# 1s.net
KiCad netlist of a schematic drawn in EAGLE
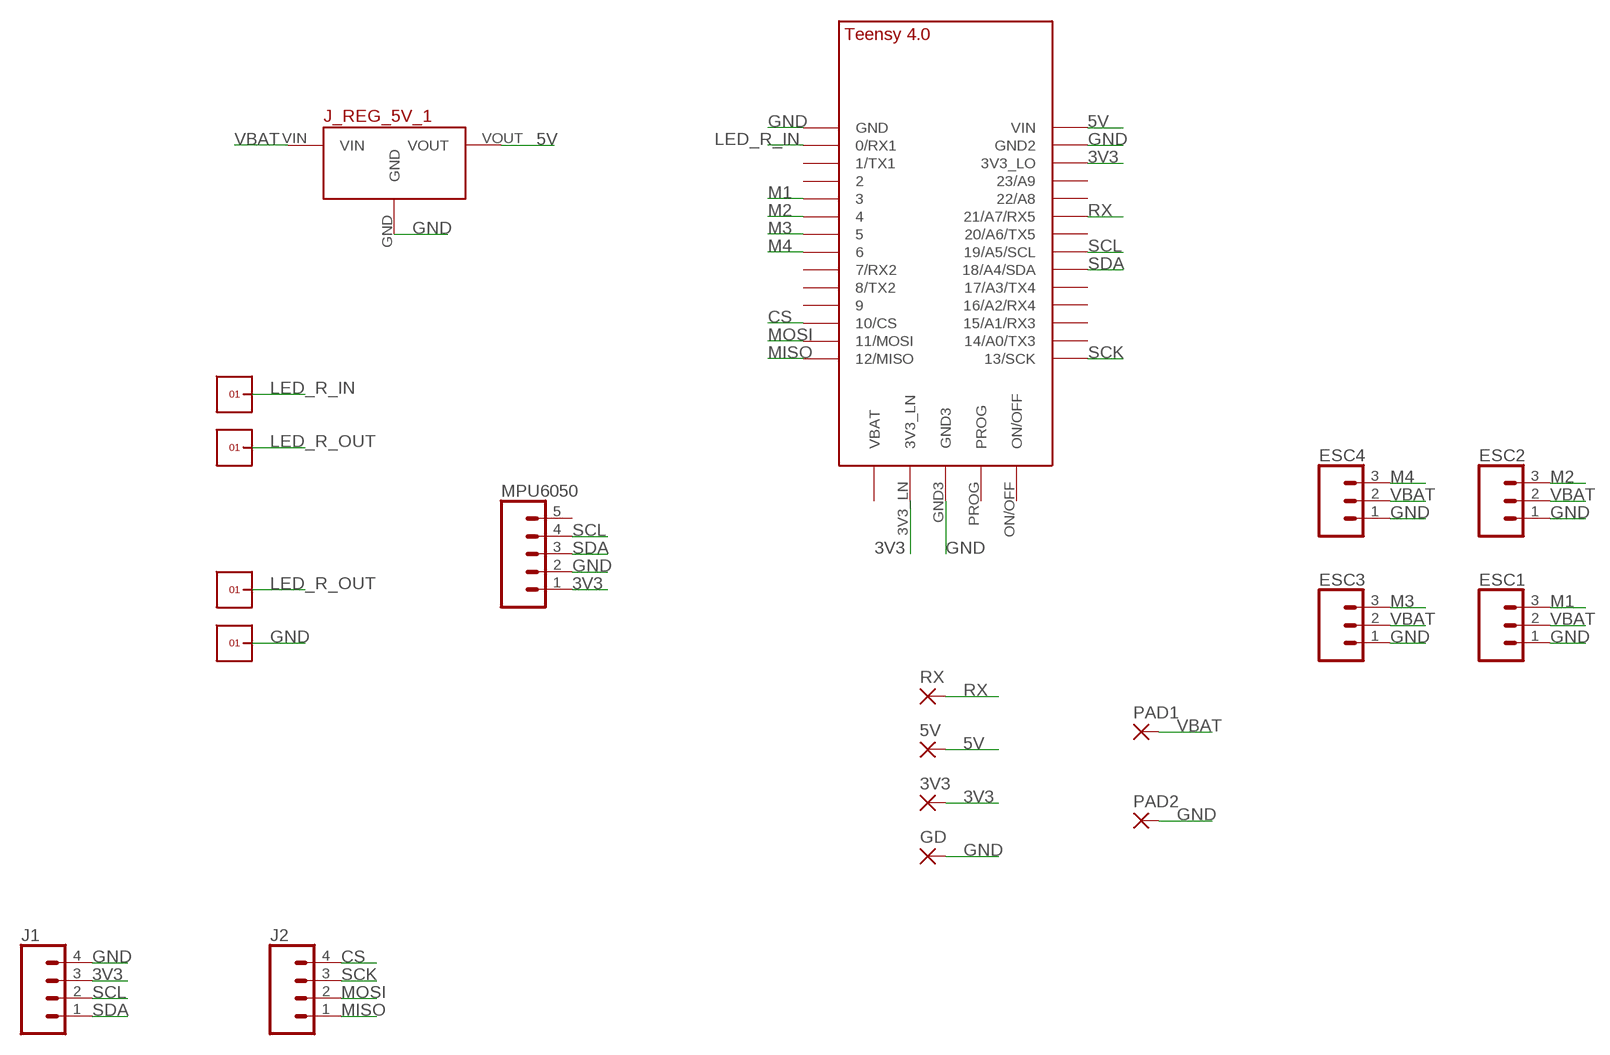
[diagram p0: schematic, sheet 1]

(export (version "E")
  (design (tool "Eeschema 10.0.6"))
  (components
    (comp (ref "3V3")
      (value "SMD2")
      (footprint "eagle-import:SMD1,27-2,54")
      (libsource (lib "eagle-import") (part "SMD2"))
    )
    (comp (ref "5V")
      (value "SMD2")
      (footprint "eagle-import:SMD1,27-2,54")
      (libsource (lib "eagle-import") (part "SMD2"))
    )
    (comp (ref "ESC1")
      (value "455-1750-1-ND")
      (footprint "eagle-import:1X03")
      (libsource (lib "eagle-import") (part "CONN_03"))
    )
    (comp (ref "ESC2")
      (value "455-1750-1-ND")
      (footprint "eagle-import:1X03")
      (libsource (lib "eagle-import") (part "CONN_03"))
    )
    (comp (ref "ESC3")
      (value "455-1750-1-ND")
      (footprint "eagle-import:1X03")
      (libsource (lib "eagle-import") (part "CONN_03"))
    )
    (comp (ref "ESC4")
      (value "455-1750-1-ND")
      (footprint "eagle-import:1X03")
      (libsource (lib "eagle-import") (part "CONN_03"))
    )
    (comp (ref "GD")
      (value "SMD2")
      (footprint "eagle-import:SMD1,27-2,54")
      (libsource (lib "eagle-import") (part "SMD2"))
    )
    (comp (ref "J1")
      (value "CONN_041X04_NO_SILK")
      (footprint "eagle-import:1X04_NO_SILK")
      (libsource (lib "eagle-import") (part "CONN_041X04_NO_SILK"))
    )
    (comp (ref "J2")
      (value "CONN_041X04_NO_SILK")
      (footprint "eagle-import:1X04_NO_SILK")
      (libsource (lib "eagle-import") (part "CONN_041X04_NO_SILK"))
    )
    (comp (ref "J_REG_5V_1")
      (value "5V_VOLTAGE_REGULATOR")
      (footprint "eagle-import:5V_VOLTAGE_REGULATOR")
      (libsource (lib "eagle-import") (part "5V_VOLTAGE_REGULATOR"))
    )
    (comp (ref "MPU6050")
      (value "CONN_05NO_SILK")
      (footprint "eagle-import:1X05_NO_SILK")
      (libsource (lib "eagle-import") (part "CONN_05NO_SILK"))
    )
    (comp (ref "PAD1")
      (value "SMD5")
      (footprint "eagle-import:SMD2,54-5,08")
      (libsource (lib "eagle-import") (part "SMD5"))
    )
    (comp (ref "PAD2")
      (value "SMD5")
      (footprint "eagle-import:SMD2,54-5,08")
      (libsource (lib "eagle-import") (part "SMD5"))
    )
    (comp (ref "RX")
      (value "SMD2")
      (footprint "eagle-import:SMD1,27-2,54")
      (libsource (lib "eagle-import") (part "SMD2"))
    )
    (comp (ref "U$1")
      (value "TEENSY_4.0")
      (footprint "eagle-import:TEENSY_4.0")
      (libsource (lib "eagle-import") (part "TEENSY_4.0"))
    )
    (comp (ref "U$3")
      (value "1X1")
      (footprint "eagle-import:1X1")
      (libsource (lib "eagle-import") (part "1X1"))
    )
    (comp (ref "U$4")
      (value "1X1")
      (footprint "eagle-import:1X1")
      (libsource (lib "eagle-import") (part "1X1"))
    )
    (comp (ref "U$6")
      (value "1X1")
      (footprint "eagle-import:1X1")
      (libsource (lib "eagle-import") (part "1X1"))
    )
    (comp (ref "U$7")
      (value "1X1")
      (footprint "eagle-import:1X1")
      (libsource (lib "eagle-import") (part "1X1"))
    )
  )
  (nets
    (net (code "1") (name "/3V3") (class "Default")
      (node (ref "3V3") (pin "1") (pinfunction "P_1") (pintype "passive"))
      (node (ref "J1") (pin "3") (pinfunction "3_3") (pintype "passive"))
      (node (ref "MPU6050") (pin "1") (pinfunction "1_1") (pintype "passive"))
      (node (ref "U$1") (pin "3V3_LN") (pinfunction "3V3_LN_3V3_LN") (pintype "bidirectional"))
      (node (ref "U$1") (pin "3V3_LO") (pinfunction "3V3_LO_3V3_LO") (pintype "bidirectional"))
    )
    (net (code "2") (name "/5V") (class "Default")
      (node (ref "5V") (pin "1") (pinfunction "P_1") (pintype "passive"))
      (node (ref "J_REG_5V_1") (pin "VOUT") (pinfunction "VOUT_VOUT") (pintype "bidirectional"))
      (node (ref "U$1") (pin "VIN") (pinfunction "VIN_VIN") (pintype "bidirectional"))
    )
    (net (code "3") (name "/CS") (class "Default")
      (node (ref "J2") (pin "4") (pinfunction "4_4") (pintype "passive"))
      (node (ref "U$1") (pin "10/CS") (pinfunction "10/CS_10/CS") (pintype "bidirectional"))
    )
    (net (code "4") (name "/GND") (class "Default")
      (node (ref "ESC1") (pin "1") (pinfunction "1_1") (pintype "passive"))
      (node (ref "ESC2") (pin "1") (pinfunction "1_1") (pintype "passive"))
      (node (ref "ESC3") (pin "1") (pinfunction "1_1") (pintype "passive"))
      (node (ref "ESC4") (pin "1") (pinfunction "1_1") (pintype "passive"))
      (node (ref "GD") (pin "1") (pinfunction "P_1") (pintype "passive"))
      (node (ref "J1") (pin "4") (pinfunction "4_4") (pintype "passive"))
      (node (ref "J_REG_5V_1") (pin "GND") (pinfunction "GND_GND") (pintype "bidirectional"))
      (node (ref "MPU6050") (pin "2") (pinfunction "2_2") (pintype "passive"))
      (node (ref "PAD2") (pin "1") (pinfunction "P_1") (pintype "passive"))
      (node (ref "U$1") (pin "GND") (pinfunction "GND_GND") (pintype "bidirectional"))
      (node (ref "U$1") (pin "GND2") (pinfunction "GND2_GND2") (pintype "bidirectional"))
      (node (ref "U$1") (pin "GND3") (pinfunction "GND3_GND3") (pintype "bidirectional"))
      (node (ref "U$7") (pin "1") (pinfunction "1_1") (pintype "bidirectional"))
    )
    (net (code "5") (name "/LED_R_IN") (class "Default")
      (node (ref "U$1") (pin "0/RX") (pinfunction "0/RX1_0/RX") (pintype "bidirectional"))
      (node (ref "U$3") (pin "1") (pinfunction "1_1") (pintype "bidirectional"))
    )
    (net (code "6") (name "/LED_R_OUT") (class "Default")
      (node (ref "U$4") (pin "1") (pinfunction "1_1") (pintype "bidirectional"))
      (node (ref "U$6") (pin "1") (pinfunction "1_1") (pintype "bidirectional"))
    )
    (net (code "7") (name "/M1") (class "Default")
      (node (ref "ESC1") (pin "3") (pinfunction "3_3") (pintype "passive"))
      (node (ref "U$1") (pin "3/CANTX") (pinfunction "3_3/CANTX") (pintype "bidirectional"))
    )
    (net (code "8") (name "/M2") (class "Default")
      (node (ref "ESC2") (pin "3") (pinfunction "3_3") (pintype "passive"))
      (node (ref "U$1") (pin "4/CANRX") (pinfunction "4_4/CANRX") (pintype "bidirectional"))
    )
    (net (code "9") (name "/M3") (class "Default")
      (node (ref "ESC3") (pin "3") (pinfunction "3_3") (pintype "passive"))
      (node (ref "U$1") (pin "5") (pinfunction "5_5") (pintype "bidirectional"))
    )
    (net (code "10") (name "/M4") (class "Default")
      (node (ref "ESC4") (pin "3") (pinfunction "3_3") (pintype "passive"))
      (node (ref "U$1") (pin "6") (pinfunction "6_6") (pintype "bidirectional"))
    )
    (net (code "11") (name "/MISO") (class "Default")
      (node (ref "J2") (pin "1") (pinfunction "1_1") (pintype "passive"))
      (node (ref "U$1") (pin "12/MISO") (pinfunction "12/MISO_12/MISO") (pintype "bidirectional"))
    )
    (net (code "12") (name "/MOSI") (class "Default")
      (node (ref "J2") (pin "2") (pinfunction "2_2") (pintype "passive"))
      (node (ref "U$1") (pin "11/MOSI") (pinfunction "11/MOSI_11/MOSI") (pintype "bidirectional"))
    )
    (net (code "13") (name "/RX") (class "Default")
      (node (ref "RX") (pin "1") (pinfunction "P_1") (pintype "passive"))
      (node (ref "U$1") (pin "21/A7") (pinfunction "21/A7/RX5_21/A7") (pintype "bidirectional"))
    )
    (net (code "14") (name "/SCK") (class "Default")
      (node (ref "J2") (pin "3") (pinfunction "3_3") (pintype "passive"))
      (node (ref "U$1") (pin "13/SCK") (pinfunction "13/SCK_13/SCK") (pintype "bidirectional"))
    )
    (net (code "15") (name "/SCL") (class "Default")
      (node (ref "J1") (pin "2") (pinfunction "2_2") (pintype "passive"))
      (node (ref "MPU6050") (pin "4") (pinfunction "4_4") (pintype "passive"))
      (node (ref "U$1") (pin "19/A5/SCL") (pinfunction "19/A5/SCL_19/A5/SCL") (pintype "bidirectional"))
    )
    (net (code "16") (name "/SDA") (class "Default")
      (node (ref "J1") (pin "1") (pinfunction "1_1") (pintype "passive"))
      (node (ref "MPU6050") (pin "3") (pinfunction "3_3") (pintype "passive"))
      (node (ref "U$1") (pin "18/A4/SDA") (pinfunction "18/A4/SDA_18/A4/SDA") (pintype "bidirectional"))
    )
    (net (code "17") (name "/VBAT") (class "Default")
      (node (ref "ESC1") (pin "2") (pinfunction "2_2") (pintype "passive"))
      (node (ref "ESC2") (pin "2") (pinfunction "2_2") (pintype "passive"))
      (node (ref "ESC3") (pin "2") (pinfunction "2_2") (pintype "passive"))
      (node (ref "ESC4") (pin "2") (pinfunction "2_2") (pintype "passive"))
      (node (ref "J_REG_5V_1") (pin "VIN") (pinfunction "VIN_VIN") (pintype "bidirectional"))
      (node (ref "PAD1") (pin "1") (pinfunction "P_1") (pintype "passive"))
    )
    (net (code "18") (name "unconnected-(MPU6050-Pad5)") (class "Default")
      (node (ref "MPU6050") (pin "5") (pinfunction "5_5") (pintype "passive"))
    )
    (net (code "19") (name "unconnected-(U$1-1{slash}TX1-Pad1{slash}TX)") (class "Default")
      (node (ref "U$1") (pin "1/TX") (pinfunction "1/TX1_1/TX") (pintype "bidirectional"))
    )
    (net (code "20") (name "unconnected-(U$1-7{slash}RX2-Pad7)") (class "Default")
      (node (ref "U$1") (pin "7") (pinfunction "7/RX2_7") (pintype "bidirectional"))
    )
    (net (code "21") (name "unconnected-(U$1-8{slash}TX2-Pad8)") (class "Default")
      (node (ref "U$1") (pin "8") (pinfunction "8/TX2_8") (pintype "bidirectional"))
    )
    (net (code "22") (name "unconnected-(U$1-9-Pad9{slash}CS)") (class "Default")
      (node (ref "U$1") (pin "9/CS") (pinfunction "9_9/CS") (pintype "bidirectional"))
    )
    (net (code "23") (name "unconnected-(U$1-14{slash}A0{slash}TX3-Pad14{slash}A0)") (class "Default")
      (node (ref "U$1") (pin "14/A0") (pinfunction "14/A0/TX3_14/A0") (pintype "bidirectional"))
    )
    (net (code "24") (name "unconnected-(U$1-15{slash}A1{slash}RX3-Pad15{slash}A1)") (class "Default")
      (node (ref "U$1") (pin "15/A1") (pinfunction "15/A1/RX3_15/A1") (pintype "bidirectional"))
    )
    (net (code "25") (name "unconnected-(U$1-16{slash}A2{slash}RX4-Pad16{slash}A2)") (class "Default")
      (node (ref "U$1") (pin "16/A2") (pinfunction "16/A2/RX4_16/A2") (pintype "bidirectional"))
    )
    (net (code "26") (name "unconnected-(U$1-17{slash}A3{slash}TX4-Pad17{slash}A3)") (class "Default")
      (node (ref "U$1") (pin "17/A3") (pinfunction "17/A3/TX4_17/A3") (pintype "bidirectional"))
    )
    (net (code "27") (name "unconnected-(U$1-20{slash}A6{slash}TX5-Pad20{slash}A6)") (class "Default")
      (node (ref "U$1") (pin "20/A6") (pinfunction "20/A6/TX5_20/A6") (pintype "bidirectional"))
    )
    (net (code "28") (name "unconnected-(U$1-Pad2)") (class "Default")
      (node (ref "U$1") (pin "2") (pinfunction "2_2") (pintype "bidirectional"))
    )
    (net (code "29") (name "unconnected-(U$1-Pad22{slash}A8)") (class "Default")
      (node (ref "U$1") (pin "22/A8") (pinfunction "22/A8_22/A8") (pintype "bidirectional"))
    )
    (net (code "30") (name "unconnected-(U$1-Pad23{slash}A9)") (class "Default")
      (node (ref "U$1") (pin "23/A9") (pinfunction "23/A9_23/A9") (pintype "bidirectional"))
    )
    (net (code "31") (name "unconnected-(U$1-PadON{slash}OFF)") (class "Default")
      (node (ref "U$1") (pin "ON/OFF") (pinfunction "ON/OFF_ON/OFF") (pintype "bidirectional"))
    )
    (net (code "32") (name "unconnected-(U$1-PadPROG)") (class "Default")
      (node (ref "U$1") (pin "PROG") (pinfunction "PROG_PROG") (pintype "bidirectional"))
    )
    (net (code "33") (name "unconnected-(U$1-VBAT-PadVBAT\\)") (class "Default")
      (node (ref "U$1") (pin "VBAT\\") (pinfunction "VBAT_VBAT\\") (pintype "bidirectional"))
    )
  )
)
